# 12_-MCU_INPUTS.net
KiCad netlist of a schematic drawn in Altium Designer
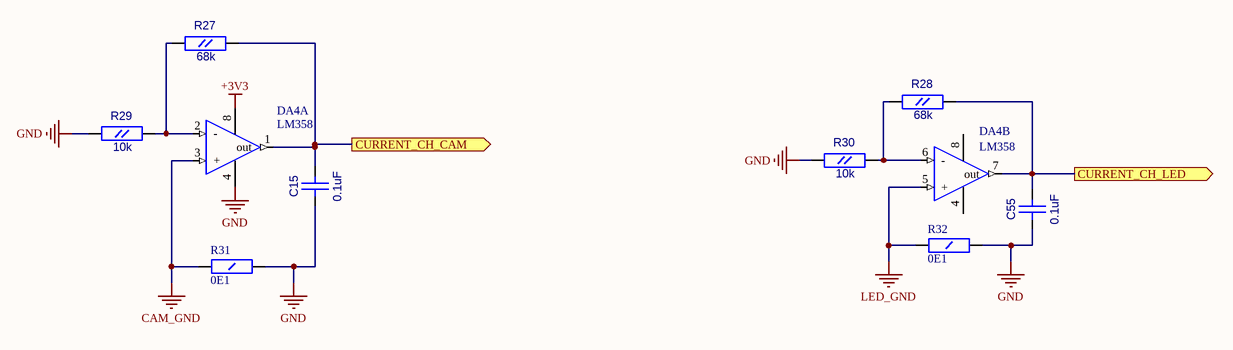
[diagram p0: [12]-MCU_INPUTS.SchDoc]

(export (version "E")
  (design (tool "Eeschema 10.0.6"))
  (components
    (comp (ref "C15")
      (value "0.1uF")
      (footprint "CC0603")
      (description "CC0603")
      (libsource (lib "fizik_lib") (part "CC0603"))
    )
    (comp (ref "C55")
      (value "0.1uF")
      (footprint "CC0603")
      (description "CC0603")
      (libsource (lib "fizik_lib") (part "CC0603"))
    )
    (comp (ref "DA4") (value "LM358") (footprint "SO-8") (libsource (lib "") (part "lm358_1")))
    (comp (ref "R27")
      (value "68k")
      (footprint "RC0603")
      (description "RC0603")
      (libsource (lib "fizik_lib") (part "RC0603"))
    )
    (comp (ref "R28")
      (value "68k")
      (footprint "RC0603")
      (description "RC0603")
      (libsource (lib "fizik_lib") (part "RC0603"))
    )
    (comp (ref "R29")
      (value "10k")
      (footprint "RC0603")
      (description "RC0603")
      (libsource (lib "fizik_lib") (part "RC0603"))
    )
    (comp (ref "R30")
      (value "10k")
      (footprint "RC0603")
      (description "RC0603")
      (libsource (lib "fizik_lib") (part "RC0603"))
    )
    (comp (ref "R31")
      (value "0E1")
      (footprint "R2512")
      (description "Resistor 2512 1W")
      (libsource (lib "fizik_lib") (part "RC2512"))
    )
    (comp (ref "R32")
      (value "0E1")
      (footprint "R2512")
      (description "Resistor 2512 1W")
      (libsource (lib "fizik_lib") (part "RC2512"))
    )
  )
  (nets
    (net (code "1") (name "+3V3") (class "Default")
      (node (ref "DA4") (pin "8") (pinfunction "V+_8") (pintype "passive"))
    )
    (net (code "2") (name "/CURRENT_CH_CAM") (class "Default")
      (node (ref "C15") (pin "2") (pinfunction "B_2") (pintype "passive"))
      (node (ref "DA4") (pin "1") (pinfunction "out_1") (pintype "output"))
      (node (ref "R27") (pin "2") (pinfunction "B_2") (pintype "passive"))
    )
    (net (code "3") (name "/CURRENT_CH_LED") (class "Default")
      (node (ref "C55") (pin "2") (pinfunction "B_2") (pintype "passive"))
      (node (ref "DA4") (pin "7") (pinfunction "out_7") (pintype "output"))
      (node (ref "R28") (pin "2") (pinfunction "B_2") (pintype "passive"))
    )
    (net (code "4") (name "CAM_GND") (class "Default")
      (node (ref "DA4") (pin "3") (pinfunction "+_3") (pintype "input"))
      (node (ref "R31") (pin "1") (pinfunction "A_1") (pintype "passive"))
    )
    (net (code "5") (name "GND") (class "Default")
      (node (ref "C15") (pin "1") (pinfunction "A_1") (pintype "passive"))
      (node (ref "C55") (pin "1") (pinfunction "A_1") (pintype "passive"))
      (node (ref "DA4") (pin "4") (pinfunction "V-_4") (pintype "passive"))
      (node (ref "R29") (pin "1") (pinfunction "A_1") (pintype "passive"))
      (node (ref "R30") (pin "1") (pinfunction "A_1") (pintype "passive"))
      (node (ref "R31") (pin "2") (pinfunction "B_2") (pintype "passive"))
      (node (ref "R32") (pin "2") (pinfunction "B_2") (pintype "passive"))
    )
    (net (code "6") (name "LED_GND") (class "Default")
      (node (ref "DA4") (pin "5") (pinfunction "+_5") (pintype "input"))
      (node (ref "R32") (pin "1") (pinfunction "A_1") (pintype "passive"))
    )
    (net (code "7") (name "Net-(DA4A--)") (class "Default")
      (node (ref "DA4") (pin "2") (pinfunction "-_2") (pintype "input"))
      (node (ref "R27") (pin "1") (pinfunction "A_1") (pintype "passive"))
      (node (ref "R29") (pin "2") (pinfunction "B_2") (pintype "passive"))
    )
    (net (code "8") (name "Net-(DA4B--)") (class "Default")
      (node (ref "DA4") (pin "6") (pinfunction "-_6") (pintype "input"))
      (node (ref "R28") (pin "1") (pinfunction "A_1") (pintype "passive"))
      (node (ref "R30") (pin "2") (pinfunction "B_2") (pintype "passive"))
    )
    (net (code "9") (name "unconnected-(DA4B-V+-Pad8)") (class "Default")
      (node (ref "DA4") (pin "8") (pinfunction "V+_8") (pintype "passive"))
    )
    (net (code "10") (name "unconnected-(DA4B-V--Pad4)") (class "Default")
      (node (ref "DA4") (pin "4") (pinfunction "V-_4") (pintype "passive"))
    )
  )
)
